# POWERSTAGE.net
KiCad netlist of a schematic drawn in Altium Designer
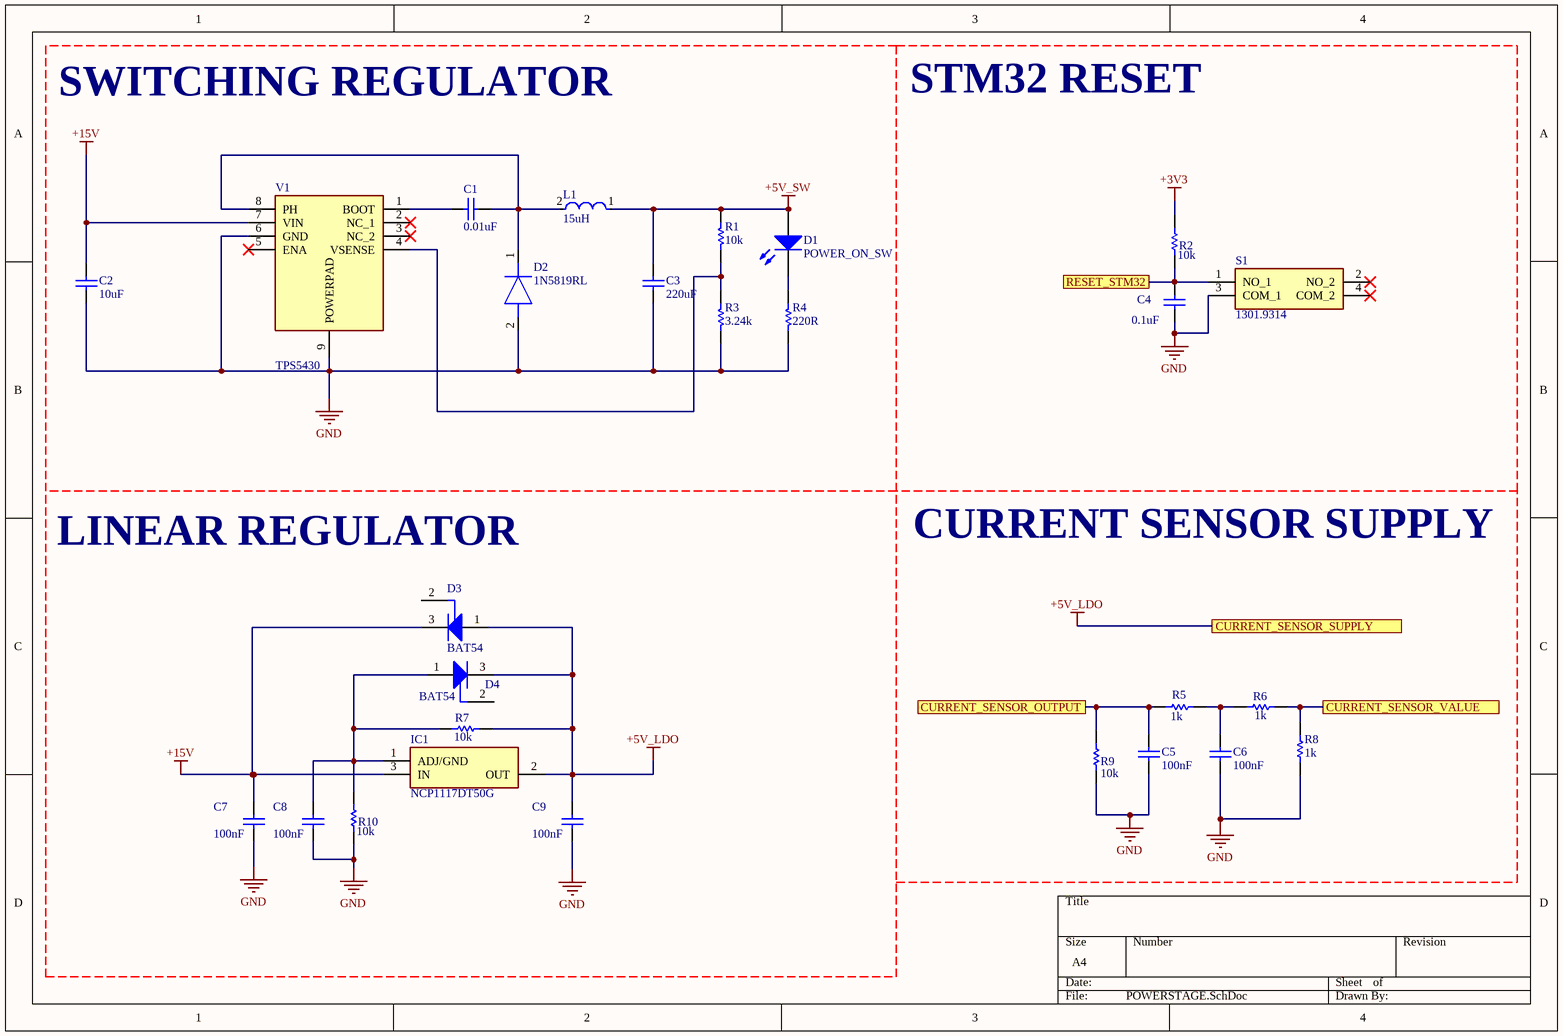
[diagram p0: POWERSTAGE.SchDoc]

(export (version "E")
  (design (tool "Eeschema 10.0.6"))
  (components
    (comp (ref "C1")
      (value "0.01uF")
      (footprint "KEMT-1206-2_N")
      (description "CAP, Ceramic, 0.1 uF, +/- 10%, 50 V, -55 to 125 degC, 1206 (3216 Metric), RoHS, Tape and Reel")
      (fields (field (name "MANUFACTURER") "Kemet"))
      (libsource (lib "Regular_used_components_2D_Symbol") (part "CAPACITOR"))
    )
    (comp (ref "C2")
      (value "10uF")
      (footprint "KEMT-1206-2_N")
      (description "CAP, Ceramic, 0.1 uF, +/- 10%, 50 V, -55 to 125 degC, 1206 (3216 Metric), RoHS, Tape and Reel")
      (fields (field (name "MANUFACTURER") "Kemet"))
      (libsource (lib "Regular_used_components_2D_Symbol") (part "CAPACITOR"))
    )
    (comp (ref "C3")
      (value "220uF")
      (footprint "KEMT-1206-2_N")
      (description "CAP, Ceramic, 0.1 uF, +/- 10%, 50 V, -55 to 125 degC, 1206 (3216 Metric), RoHS, Tape and Reel")
      (fields (field (name "MANUFACTURER") "Kemet"))
      (libsource (lib "Regular_used_components_2D_Symbol") (part "CAPACITOR"))
    )
    (comp (ref "C4")
      (value "0.1uF")
      (footprint "KEMT-1206-2_N")
      (description "CAP, Ceramic, 0.1 uF, +/- 10%, 50 V, -55 to 125 degC, 1206 (3216 Metric), RoHS, Tape and Reel")
      (fields (field (name "MANUFACTURER") "Kemet"))
      (libsource (lib "Regular_used_components_2D_Symbol") (part "CAPACITOR"))
    )
    (comp (ref "C5")
      (value "100nF")
      (footprint "KEMT-1206-2_N")
      (description "CAP, Ceramic, 0.1 uF, +/- 10%, 50 V, -55 to 125 degC, 1206 (3216 Metric), RoHS, Tape and Reel")
      (fields (field (name "MANUFACTURER") "Kemet"))
      (libsource (lib "Schlib1_TSAL_LV_3.1") (part "CMP-1037-04202-2"))
    )
    (comp (ref "C6")
      (value "100nF")
      (footprint "KEMT-1206-2_N")
      (description "CAP, Ceramic, 0.1 uF, +/- 10%, 50 V, -55 to 125 degC, 1206 (3216 Metric), RoHS, Tape and Reel")
      (fields (field (name "MANUFACTURER") "Kemet"))
      (libsource (lib "Schlib1_TSAL_LV_3.1") (part "CMP-1037-04202-2"))
    )
    (comp (ref "C7")
      (value "100nF")
      (footprint "KEMT-1206-2_N")
      (description "CAP, Ceramic, 0.1 uF, +/- 10%, 50 V, -55 to 125 degC, 1206 (3216 Metric), RoHS, Tape and Reel")
      (fields (field (name "MANUFACTURER") "Kemet"))
      (libsource (lib "Schlib1_TSAL_LV_3.1") (part "CMP-1037-04202-2"))
    )
    (comp (ref "C8")
      (value "100nF")
      (footprint "KEMT-1206-2_N")
      (description "CAP, Ceramic, 0.1 uF, +/- 10%, 50 V, -55 to 125 degC, 1206 (3216 Metric), RoHS, Tape and Reel")
      (fields (field (name "MANUFACTURER") "Kemet"))
      (libsource (lib "Schlib1_TSAL_LV_3.1") (part "CMP-1037-04202-2"))
    )
    (comp (ref "C9")
      (value "100nF")
      (footprint "KEMT-1206-2_N")
      (description "CAP, Ceramic, 0.1 uF, +/- 10%, 50 V, -55 to 125 degC, 1206 (3216 Metric), RoHS, Tape and Reel")
      (fields (field (name "MANUFACTURER") "Kemet"))
      (libsource (lib "Schlib1_TSAL_LV_3.1") (part "CMP-1037-04202-2"))
    )
    (comp (ref "D1")
      (value "POWER_ON_SW")
      (footprint "3.2X1.6X1.1")
      (description "Typical RED, GREEN, YELLOW, AMBER GaAs LED")
      (fields (field (name "PUBLISHER") "Altium Limited"))
      (libsource (lib "Miscellaneous Devices") (part "LED2"))
    )
    (comp (ref "D2")
      (value "1N5819RL")
      (footprint "SamacSys:DIOAD1414W86L464D238")
      (description "Diode")
      (fields (field (name "MOUSER PART NUMBER") "511-1N5819-TR"))
      (libsource (lib "*") (part "1N5819RL"))
    )
    (comp (ref "D3")
      (value "BAT54")
      (footprint "INF-SOT23_N")
      (description "Silicon Schottky Diode, SOT23, Reel, Green")
      (fields (field (name "MANUFACTURER") "Infineon"))
      (libsource (lib "Schlib1") (part "CMP-1182-00010-1"))
    )
    (comp (ref "D4")
      (value "BAT54")
      (footprint "INF-SOT23_N")
      (description "Silicon Schottky Diode, SOT23, Reel, Green")
      (fields (field (name "MANUFACTURER") "Infineon"))
      (libsource (lib "Schlib1") (part "CMP-1182-00010-1"))
    )
    (comp (ref "IC1")
      (value "NCP1117DT50G")
      (footprint "Regular_used_components_3D_Symbol:LM317MADTRKG")
      (description "Integrated Circuit")
      (fields (field (name "MOUSER PART NUMBER") "863-NCP1117DT50G"))
      (libsource (lib "*") (part "NCP1117DT50G"))
    )
    (comp (ref "L1")
      (value "15uH")
      (footprint "FP-IR02-MFG")
      (description "IR-2 10 10% B08")
      (fields (field (name "TOLERANCE") "10%") (field (name "OBSOLETE PART") "true"))
      (libsource (lib "Regular_used_components_2D_Symbol") (part "CMP-03630-000001-1"))
    )
    (comp (ref "R1")
      (value "10k")
      (footprint "RESC3216X60X45NL10T20 - duplicate")
      (fields (field (name "PART NUMBER") "CRCW120647K0FKEA") (field (name "MANUFACTURER") "Vishay Dale"))
      (libsource (lib "Regular_used_components_2D_Symbol") (part "CMP-2003-02213-1"))
    )
    (comp (ref "R2")
      (value "10k")
      (footprint "RESC3216X60X45NL10T20 - duplicate")
      (fields (field (name "PART NUMBER") "CRCW120647K0FKEA") (field (name "MANUFACTURER") "Vishay Dale"))
      (libsource (lib "Regular_used_components_2D_Symbol") (part "CMP-2003-02213-1"))
    )
    (comp (ref "R3")
      (value "3.24k")
      (footprint "RESC3216X60X45NL10T20 - duplicate")
      (fields (field (name "PART NUMBER") "CRCW120647K0FKEA") (field (name "MANUFACTURER") "Vishay Dale"))
      (libsource (lib "Regular_used_components_2D_Symbol") (part "CMP-2003-02213-1"))
    )
    (comp (ref "R4")
      (value "220R")
      (footprint "RESC3216X60X45NL10T20 - duplicate")
      (fields (field (name "PART NUMBER") "CRCW120647K0FKEA") (field (name "MANUFACTURER") "Vishay Dale"))
      (libsource (lib "Regular_used_components_2D_Symbol") (part "CMP-2003-02213-1"))
    )
    (comp (ref "R5")
      (value "1k")
      (footprint "R1206")
      (fields (field (name "PART NUMBER") "CRCW120647K0FKEA") (field (name "MANUFACTURER") "Vishay Dale"))
      (libsource (lib "SamacSys") (part "RES"))
    )
    (comp (ref "R6")
      (value "1k")
      (footprint "R1206")
      (fields (field (name "PART NUMBER") "CRCW120647K0FKEA") (field (name "MANUFACTURER") "Vishay Dale"))
      (libsource (lib "SamacSys") (part "RES"))
    )
    (comp (ref "R7")
      (value "10k")
      (footprint "RESC3216X60X45NL10T20 - duplicate")
      (fields (field (name "PART NUMBER") "CRCW120647K0FKEA") (field (name "MANUFACTURER") "Vishay Dale"))
      (libsource (lib "Regular_used_components_2D_Symbol") (part "CMP-2003-02213-1"))
    )
    (comp (ref "R8")
      (value "1k")
      (footprint "R1206")
      (fields (field (name "PART NUMBER") "CRCW120647K0FKEA") (field (name "MANUFACTURER") "Vishay Dale"))
      (libsource (lib "SamacSys") (part "RES"))
    )
    (comp (ref "R9")
      (value "10k")
      (footprint "R1206")
      (fields (field (name "PART NUMBER") "CRCW120647K0FKEA") (field (name "MANUFACTURER") "Vishay Dale"))
      (libsource (lib "SamacSys") (part "RES"))
    )
    (comp (ref "R10")
      (value "10k")
      (footprint "RESC3216X60X45NL10T20 - duplicate")
      (fields (field (name "PART NUMBER") "CRCW120647K0FKEA") (field (name "MANUFACTURER") "Vishay Dale"))
      (libsource (lib "Regular_used_components_2D_Symbol") (part "CMP-2003-02213-1"))
    )
    (comp (ref "S1")
      (value "1301.9314")
      (footprint "Regular_used_components_3D_Symbol:13019319")
      (description "Switch")
      (fields (field (name "MOUSER PART NUMBER") "693-1301.9314"))
      (libsource (lib "*") (part "1301.9314"))
    )
    (comp (ref "V1") (value "TPS5430") (footprint "TPS5430") (libsource (lib "Schlib1") (part "TPS5430")))
  )
  (nets
    (net (code "1") (name "+3V3") (class "Default")
      (node (ref "R2") (pin "2") (pinfunction "2_2") (pintype "passive"))
    )
    (net (code "2") (name "+5V_LDO") (class "Default")
      (node (ref "C9") (pin "1") (pinfunction "1_1") (pintype "passive"))
      (node (ref "D3") (pin "1") (pinfunction "A_1") (pintype "passive"))
      (node (ref "D4") (pin "3") (pinfunction "K_3") (pintype "passive"))
      (node (ref "IC1") (pin "2") (pinfunction "OUT_2") (pintype "passive"))
      (node (ref "R7") (pin "1") (pinfunction "1_1") (pintype "passive"))
    )
    (net (code "3") (name "+5V_SW") (class "Default")
      (node (ref "C3") (pin "2") (pinfunction "2_2") (pintype "passive"))
      (node (ref "D1") (pin "1") (pinfunction "A_1") (pintype "passive"))
      (node (ref "L1") (pin "1") (pinfunction "1_1") (pintype "passive"))
      (node (ref "R1") (pin "2") (pinfunction "2_2") (pintype "passive"))
    )
    (net (code "4") (name "+15V") (class "Default")
      (node (ref "C2") (pin "2") (pinfunction "2_2") (pintype "passive"))
      (node (ref "C7") (pin "1") (pinfunction "1_1") (pintype "passive"))
      (node (ref "D3") (pin "3") (pinfunction "K_3") (pintype "passive"))
      (node (ref "IC1") (pin "3") (pinfunction "IN_3") (pintype "passive"))
      (node (ref "V1") (pin "7") (pinfunction "VIN_7") (pintype "passive"))
    )
    (net (code "5") (name "/CURRENT_SENSOR_OUTPUT") (class "Default")
      (node (ref "C5") (pin "2") (pinfunction "2_2") (pintype "passive"))
      (node (ref "R5") (pin "2") (pinfunction "2_2") (pintype "passive"))
      (node (ref "R9") (pin "1") (pinfunction "1_1") (pintype "passive"))
    )
    (net (code "6") (name "/CURRENT_SENSOR_VALUE") (class "Default")
      (node (ref "R6") (pin "1") (pinfunction "1_1") (pintype "passive"))
      (node (ref "R8") (pin "1") (pinfunction "1_1") (pintype "passive"))
    )
    (net (code "7") (name "/RESET_STM32") (class "Default")
      (node (ref "C4") (pin "2") (pinfunction "2_2") (pintype "passive"))
      (node (ref "R2") (pin "1") (pinfunction "1_1") (pintype "passive"))
      (node (ref "S1") (pin "1") (pinfunction "NO_1_1") (pintype "passive"))
    )
    (net (code "8") (name "GND") (class "Default")
      (node (ref "C2") (pin "1") (pinfunction "1_1") (pintype "passive"))
      (node (ref "C3") (pin "1") (pinfunction "1_1") (pintype "passive"))
      (node (ref "C4") (pin "1") (pinfunction "1_1") (pintype "passive"))
      (node (ref "C5") (pin "1") (pinfunction "1_1") (pintype "passive"))
      (node (ref "C6") (pin "1") (pinfunction "1_1") (pintype "passive"))
      (node (ref "C7") (pin "2") (pinfunction "2_2") (pintype "passive"))
      (node (ref "C8") (pin "2") (pinfunction "2_2") (pintype "passive"))
      (node (ref "C9") (pin "2") (pinfunction "2_2") (pintype "passive"))
      (node (ref "D2") (pin "2") (pinfunction "A_2") (pintype "passive"))
      (node (ref "R10") (pin "1") (pinfunction "1_1") (pintype "passive"))
      (node (ref "R3") (pin "1") (pinfunction "1_1") (pintype "passive"))
      (node (ref "R4") (pin "1") (pinfunction "1_1") (pintype "passive"))
      (node (ref "R8") (pin "2") (pinfunction "2_2") (pintype "passive"))
      (node (ref "R9") (pin "2") (pinfunction "2_2") (pintype "passive"))
      (node (ref "S1") (pin "3") (pinfunction "COM_1_3") (pintype "passive"))
      (node (ref "V1") (pin "6") (pinfunction "GND_6") (pintype "passive"))
      (node (ref "V1") (pin "9") (pinfunction "POWERPAD_9") (pintype "passive"))
    )
    (net (code "9") (name "Net-(C6-Pad2)") (class "Default")
      (node (ref "C6") (pin "2") (pinfunction "2_2") (pintype "passive"))
      (node (ref "R5") (pin "1") (pinfunction "1_1") (pintype "passive"))
      (node (ref "R6") (pin "2") (pinfunction "2_2") (pintype "passive"))
    )
    (net (code "10") (name "Net-(D1-K)") (class "Default")
      (node (ref "D1") (pin "2") (pinfunction "K_2") (pintype "passive"))
      (node (ref "R4") (pin "2") (pinfunction "2_2") (pintype "passive"))
    )
    (net (code "11") (name "Net-(D2-K)") (class "Default")
      (node (ref "C1") (pin "1") (pinfunction "1_1") (pintype "passive"))
      (node (ref "D2") (pin "1") (pinfunction "K_1") (pintype "passive"))
      (node (ref "L1") (pin "2") (pinfunction "2_2") (pintype "passive"))
      (node (ref "V1") (pin "8") (pinfunction "PH_8") (pintype "passive"))
    )
    (net (code "12") (name "Net-(D4-A)") (class "Default")
      (node (ref "C8") (pin "1") (pinfunction "1_1") (pintype "passive"))
      (node (ref "D4") (pin "1") (pinfunction "A_1") (pintype "passive"))
      (node (ref "IC1") (pin "1") (pinfunction "ADJ/GND_1") (pintype "passive"))
      (node (ref "R10") (pin "2") (pinfunction "2_2") (pintype "passive"))
      (node (ref "R7") (pin "2") (pinfunction "2_2") (pintype "passive"))
    )
    (net (code "13") (name "Net-(V1-BOOT)") (class "Default")
      (node (ref "C1") (pin "2") (pinfunction "2_2") (pintype "passive"))
      (node (ref "V1") (pin "1") (pinfunction "BOOT_1") (pintype "passive"))
    )
    (net (code "14") (name "Net-(V1-VSENSE)") (class "Default")
      (node (ref "R1") (pin "1") (pinfunction "1_1") (pintype "passive"))
      (node (ref "R3") (pin "2") (pinfunction "2_2") (pintype "passive"))
      (node (ref "V1") (pin "4") (pinfunction "VSENSE_4") (pintype "passive"))
    )
    (net (code "15") (name "unconnected-(D3-NC-Pad2)") (class "Default")
      (node (ref "D3") (pin "2") (pinfunction "NC_2") (pintype "passive"))
    )
    (net (code "16") (name "unconnected-(D4-NC-Pad2)") (class "Default")
      (node (ref "D4") (pin "2") (pinfunction "NC_2") (pintype "passive"))
    )
    (net (code "17") (name "unconnected-(S1-COM_2-Pad4)") (class "Default")
      (node (ref "S1") (pin "4") (pinfunction "COM_2_4") (pintype "passive+no_connect"))
    )
    (net (code "18") (name "unconnected-(S1-NO_2-Pad2)") (class "Default")
      (node (ref "S1") (pin "2") (pinfunction "NO_2_2") (pintype "passive+no_connect"))
    )
    (net (code "19") (name "unconnected-(V1-ENA-Pad5)") (class "Default")
      (node (ref "V1") (pin "5") (pinfunction "ENA_5") (pintype "passive+no_connect"))
    )
    (net (code "20") (name "unconnected-(V1-NC_1-Pad2)") (class "Default")
      (node (ref "V1") (pin "2") (pinfunction "NC_1_2") (pintype "passive+no_connect"))
    )
    (net (code "21") (name "unconnected-(V1-NC_2-Pad3)") (class "Default")
      (node (ref "V1") (pin "3") (pinfunction "NC_2_3") (pintype "passive+no_connect"))
    )
  )
)
